# Cable.net
KiCad netlist of a schematic drawn in Altium Designer
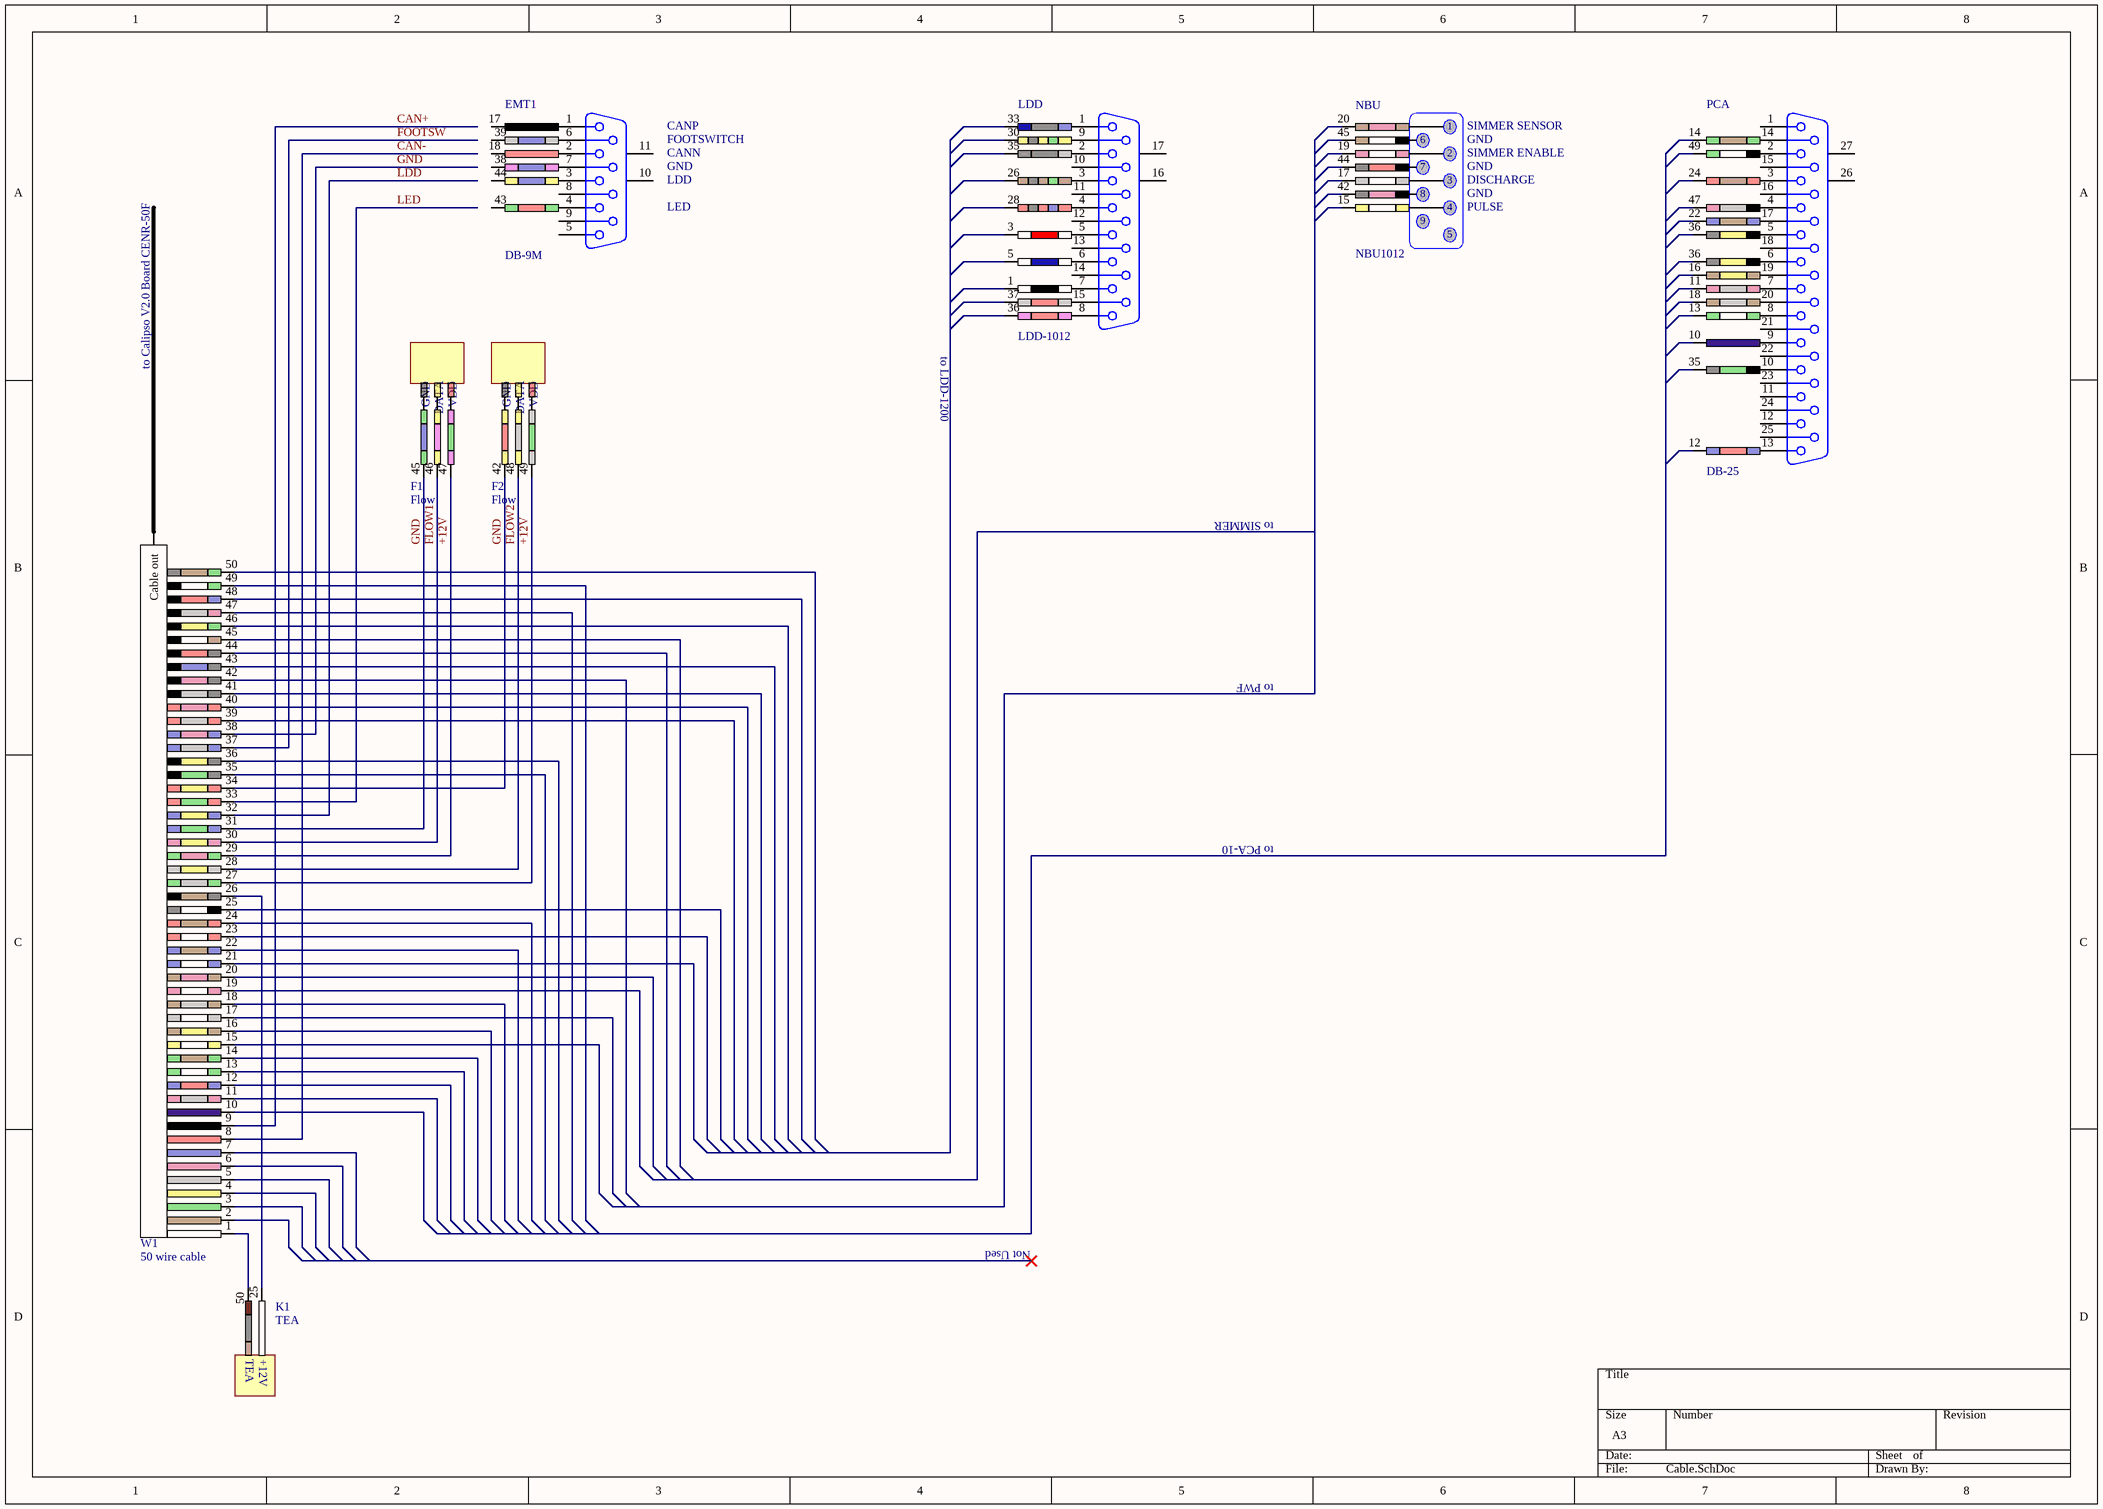
[diagram p0: Cable.SchDoc]

(export (version "E")
  (design (tool "Eeschema 10.0.6"))
  (components
    (comp (ref "EMT1") (value "DB-9M") (libsource (lib "CENR50-LaserCable") (part "Emmiter")))
    (comp (ref "F1")
      (value "Flow")
      (description "Flow sensor")
      (libsource (lib "CENR50-LaserCable") (part "Flow Sensor"))
    )
    (comp (ref "F2")
      (value "Flow")
      (description "Flow sensor 2")
      (libsource (lib "CENR50-LaserCable") (part "Flow Sensor 2"))
    )
    (comp (ref "K1")
      (value "TEA")
      (description "Termo electrical assembly")
      (libsource (lib "CENR50-LaserCable") (part "TEA"))
    )
    (comp (ref "LDD") (value "LDD-1012") (libsource (lib "CENR50-LaserCable") (part "LDD-1012")))
    (comp (ref "NBU") (value "NBU1012") (libsource (lib "CENR50-LaserCable") (part "NBU")))
    (comp (ref "PCA") (value "DB-25") (libsource (lib "CENR50-LaserCable") (part "PCA-10_1")))
    (comp (ref "W1") (value "50 wire cable") (libsource (lib "CENR50-LaserCable") (part "Cable-50wire")))
  )
  (nets
    (net (code "1") (name "/+12V") (class "Default")
      (node (ref "W1") (pin "27") (pinfunction "27_27") (pintype "passive"))
      (node (ref "W1") (pin "29") (pinfunction "29_29") (pintype "passive"))
    )
    (net (code "2") (name "/CAN+") (class "Default")
      (node (ref "W1") (pin "9") (pinfunction "9_9") (pintype "passive"))
    )
    (net (code "3") (name "/CAN-") (class "Default")
      (node (ref "W1") (pin "8") (pinfunction "8_8") (pintype "passive"))
    )
    (net (code "4") (name "/FLOW1") (class "Default")
      (node (ref "W1") (pin "30") (pinfunction "30_30") (pintype "passive"))
    )
    (net (code "5") (name "/FLOW2") (class "Default")
      (node (ref "W1") (pin "28") (pinfunction "28_28") (pintype "passive"))
    )
    (net (code "6") (name "/FOOTSW") (class "Default")
      (node (ref "W1") (pin "37") (pinfunction "37_37") (pintype "passive"))
    )
    (net (code "7") (name "/GND") (class "Default")
      (node (ref "W1") (pin "31") (pinfunction "31_31") (pintype "passive"))
      (node (ref "W1") (pin "34") (pinfunction "34_34") (pintype "passive"))
      (node (ref "W1") (pin "38") (pinfunction "38_38") (pintype "passive"))
    )
    (net (code "8") (name "/LDD") (class "Default")
      (node (ref "W1") (pin "32") (pinfunction "32_32") (pintype "passive"))
    )
    (net (code "9") (name "/LED") (class "Default")
      (node (ref "W1") (pin "33") (pinfunction "33_33") (pintype "passive"))
    )
    (net (code "10") (name "Net-(K1-Pad25)") (class "Default")
      (node (ref "K1") (pin "25") (pinfunction "25_25") (pintype "passive"))
      (node (ref "W1") (pin "26") (pinfunction "26_26") (pintype "passive"))
    )
    (net (code "11") (name "unconnected-(EMT1-MH1-Pad10)") (class "Default")
      (node (ref "EMT1") (pin "10") (pinfunction "MH1_10") (pintype "passive"))
    )
    (net (code "12") (name "unconnected-(EMT1-MH2-Pad11)") (class "Default")
      (node (ref "EMT1") (pin "11") (pinfunction "MH2_11") (pintype "passive"))
    )
    (net (code "13") (name "unconnected-(EMT1-Pad1)") (class "Default")
      (node (ref "EMT1") (pin "1") (pinfunction "1_1") (pintype "passive"))
    )
    (net (code "14") (name "unconnected-(EMT1-Pad2)") (class "Default")
      (node (ref "EMT1") (pin "2") (pinfunction "2_2") (pintype "passive"))
    )
    (net (code "15") (name "unconnected-(EMT1-Pad3)") (class "Default")
      (node (ref "EMT1") (pin "3") (pinfunction "3_3") (pintype "passive"))
    )
    (net (code "16") (name "unconnected-(EMT1-Pad4)") (class "Default")
      (node (ref "EMT1") (pin "4") (pinfunction "4_4") (pintype "passive"))
    )
    (net (code "17") (name "unconnected-(EMT1-Pad5)") (class "Default")
      (node (ref "EMT1") (pin "5") (pinfunction "5_5") (pintype "passive"))
    )
    (net (code "18") (name "unconnected-(EMT1-Pad6)") (class "Default")
      (node (ref "EMT1") (pin "6") (pinfunction "6_6") (pintype "passive"))
    )
    (net (code "19") (name "unconnected-(EMT1-Pad7)") (class "Default")
      (node (ref "EMT1") (pin "7") (pinfunction "7_7") (pintype "passive"))
    )
    (net (code "20") (name "unconnected-(EMT1-Pad8)") (class "Default")
      (node (ref "EMT1") (pin "8") (pinfunction "8_8") (pintype "passive"))
    )
    (net (code "21") (name "unconnected-(EMT1-Pad9)") (class "Default")
      (node (ref "EMT1") (pin "9") (pinfunction "9_9") (pintype "passive"))
    )
    (net (code "22") (name "unconnected-(EMT1-Pad17)") (class "Default")
      (node (ref "EMT1") (pin "17") (pinfunction "17_17") (pintype "passive"))
    )
    (net (code "23") (name "unconnected-(EMT1-Pad18)") (class "Default")
      (node (ref "EMT1") (pin "18") (pinfunction "18_18") (pintype "passive"))
    )
    (net (code "24") (name "unconnected-(EMT1-Pad38)") (class "Default")
      (node (ref "EMT1") (pin "38") (pinfunction "38_38") (pintype "passive"))
    )
    (net (code "25") (name "unconnected-(EMT1-Pad39)") (class "Default")
      (node (ref "EMT1") (pin "39") (pinfunction "39_39") (pintype "passive"))
    )
    (net (code "26") (name "unconnected-(EMT1-Pad43)") (class "Default")
      (node (ref "EMT1") (pin "43") (pinfunction "43_43") (pintype "passive"))
    )
    (net (code "27") (name "unconnected-(EMT1-Pad44)") (class "Default")
      (node (ref "EMT1") (pin "44") (pinfunction "44_44") (pintype "passive"))
    )
    (net (code "28") (name "unconnected-(F1-Pad45)") (class "Default")
      (node (ref "F1") (pin "45") (pinfunction "45_45") (pintype "passive"))
    )
    (net (code "29") (name "unconnected-(F1-Pad46)") (class "Default")
      (node (ref "F1") (pin "46") (pinfunction "46_46") (pintype "passive"))
    )
    (net (code "30") (name "unconnected-(F1-Pad47)") (class "Default")
      (node (ref "F1") (pin "47") (pinfunction "47_47") (pintype "passive"))
    )
    (net (code "31") (name "unconnected-(F2-Pad42)") (class "Default")
      (node (ref "F2") (pin "42") (pinfunction "42_42") (pintype "passive"))
    )
    (net (code "32") (name "unconnected-(F2-Pad48)") (class "Default")
      (node (ref "F2") (pin "48") (pinfunction "48_48") (pintype "passive"))
    )
    (net (code "33") (name "unconnected-(F2-Pad49)") (class "Default")
      (node (ref "F2") (pin "49") (pinfunction "49_49") (pintype "passive"))
    )
    (net (code "34") (name "unconnected-(K1-Pad50)") (class "Default")
      (node (ref "K1") (pin "50") (pinfunction "50_50") (pintype "passive"))
    )
    (net (code "35") (name "unconnected-(LDD-MH1-Pad16)") (class "Default")
      (node (ref "LDD") (pin "16") (pinfunction "MH1_16") (pintype "passive"))
    )
    (net (code "36") (name "unconnected-(LDD-MH2-Pad17)") (class "Default")
      (node (ref "LDD") (pin "17") (pinfunction "MH2_17") (pintype "passive"))
    )
    (net (code "37") (name "unconnected-(LDD-Pad1)") (class "Default")
      (node (ref "LDD") (pin "1") (pinfunction "1_1") (pintype "passive"))
    )
    (net (code "38") (name "unconnected-(LDD-Pad1)_1") (class "Default")
      (node (ref "LDD") (pin "1") (pinfunction "1_1") (pintype "passive"))
    )
    (net (code "39") (name "unconnected-(LDD-Pad2)") (class "Default")
      (node (ref "LDD") (pin "2") (pinfunction "2_2") (pintype "passive"))
    )
    (net (code "40") (name "unconnected-(LDD-Pad3)") (class "Default")
      (node (ref "LDD") (pin "3") (pinfunction "3_3") (pintype "passive"))
    )
    (net (code "41") (name "unconnected-(LDD-Pad3)_1") (class "Default")
      (node (ref "LDD") (pin "3") (pinfunction "3_3") (pintype "passive"))
    )
    (net (code "42") (name "unconnected-(LDD-Pad4)") (class "Default")
      (node (ref "LDD") (pin "4") (pinfunction "4_4") (pintype "passive"))
    )
    (net (code "43") (name "unconnected-(LDD-Pad5)") (class "Default")
      (node (ref "LDD") (pin "5") (pinfunction "5_5") (pintype "passive"))
    )
    (net (code "44") (name "unconnected-(LDD-Pad5)_1") (class "Default")
      (node (ref "LDD") (pin "5") (pinfunction "5_5") (pintype "passive"))
    )
    (net (code "45") (name "unconnected-(LDD-Pad6)") (class "Default")
      (node (ref "LDD") (pin "6") (pinfunction "6_6") (pintype "passive"))
    )
    (net (code "46") (name "unconnected-(LDD-Pad7)") (class "Default")
      (node (ref "LDD") (pin "7") (pinfunction "7_7") (pintype "passive"))
    )
    (net (code "47") (name "unconnected-(LDD-Pad8)") (class "Default")
      (node (ref "LDD") (pin "8") (pinfunction "8_8") (pintype "passive"))
    )
    (net (code "48") (name "unconnected-(LDD-Pad9)") (class "Default")
      (node (ref "LDD") (pin "9") (pinfunction "9_9") (pintype "passive"))
    )
    (net (code "49") (name "unconnected-(LDD-Pad10)") (class "Default")
      (node (ref "LDD") (pin "10") (pinfunction "10_10") (pintype "passive"))
    )
    (net (code "50") (name "unconnected-(LDD-Pad11)") (class "Default")
      (node (ref "LDD") (pin "11") (pinfunction "11_11") (pintype "passive"))
    )
    (net (code "51") (name "unconnected-(LDD-Pad12)") (class "Default")
      (node (ref "LDD") (pin "12") (pinfunction "12_12") (pintype "passive"))
    )
    (net (code "52") (name "unconnected-(LDD-Pad13)") (class "Default")
      (node (ref "LDD") (pin "13") (pinfunction "13_13") (pintype "passive"))
    )
    (net (code "53") (name "unconnected-(LDD-Pad14)") (class "Default")
      (node (ref "LDD") (pin "14") (pinfunction "14_14") (pintype "passive"))
    )
    (net (code "54") (name "unconnected-(LDD-Pad15)") (class "Default")
      (node (ref "LDD") (pin "15") (pinfunction "15_15") (pintype "passive"))
    )
    (net (code "55") (name "unconnected-(LDD-Pad26)") (class "Default")
      (node (ref "LDD") (pin "26") (pinfunction "26_26") (pintype "passive"))
    )
    (net (code "56") (name "unconnected-(LDD-Pad28)") (class "Default")
      (node (ref "LDD") (pin "28") (pinfunction "28_28") (pintype "passive"))
    )
    (net (code "57") (name "unconnected-(LDD-Pad30)") (class "Default")
      (node (ref "LDD") (pin "30") (pinfunction "30_30") (pintype "passive"))
    )
    (net (code "58") (name "unconnected-(LDD-Pad33)") (class "Default")
      (node (ref "LDD") (pin "33") (pinfunction "33_33") (pintype "passive"))
    )
    (net (code "59") (name "unconnected-(LDD-Pad35)") (class "Default")
      (node (ref "LDD") (pin "35") (pinfunction "35_35") (pintype "passive"))
    )
    (net (code "60") (name "unconnected-(LDD-Pad36)") (class "Default")
      (node (ref "LDD") (pin "36") (pinfunction "36_36") (pintype "passive"))
    )
    (net (code "61") (name "unconnected-(LDD-Pad37)") (class "Default")
      (node (ref "LDD") (pin "37") (pinfunction "37_37") (pintype "passive"))
    )
    (net (code "62") (name "unconnected-(NBU-Pad15)") (class "Default")
      (node (ref "NBU") (pin "15") (pinfunction "15_15") (pintype "passive"))
    )
    (net (code "63") (name "unconnected-(NBU-Pad17)") (class "Default")
      (node (ref "NBU") (pin "17") (pinfunction "17_17") (pintype "passive"))
    )
    (net (code "64") (name "unconnected-(NBU-Pad19)") (class "Default")
      (node (ref "NBU") (pin "19") (pinfunction "19_19") (pintype "passive"))
    )
    (net (code "65") (name "unconnected-(NBU-Pad20)") (class "Default")
      (node (ref "NBU") (pin "20") (pinfunction "20_20") (pintype "passive"))
    )
    (net (code "66") (name "unconnected-(NBU-Pad42)") (class "Default")
      (node (ref "NBU") (pin "42") (pinfunction "42_42") (pintype "passive"))
    )
    (net (code "67") (name "unconnected-(NBU-Pad44)") (class "Default")
      (node (ref "NBU") (pin "44") (pinfunction "44_44") (pintype "passive"))
    )
    (net (code "68") (name "unconnected-(NBU-Pad45)") (class "Default")
      (node (ref "NBU") (pin "45") (pinfunction "45_45") (pintype "passive"))
    )
    (net (code "69") (name "unconnected-(PCA-MH1-Pad26)") (class "Default")
      (node (ref "PCA") (pin "26") (pinfunction "MH1_26") (pintype "passive"))
    )
    (net (code "70") (name "unconnected-(PCA-MH2-Pad27)") (class "Default")
      (node (ref "PCA") (pin "27") (pinfunction "MH2_27") (pintype "passive"))
    )
    (net (code "71") (name "unconnected-(PCA-Pad1)") (class "Default")
      (node (ref "PCA") (pin "1") (pinfunction "1_1") (pintype "passive"))
    )
    (net (code "72") (name "unconnected-(PCA-Pad2)") (class "Default")
      (node (ref "PCA") (pin "2") (pinfunction "2_2") (pintype "passive"))
    )
    (net (code "73") (name "unconnected-(PCA-Pad3)") (class "Default")
      (node (ref "PCA") (pin "3") (pinfunction "3_3") (pintype "passive"))
    )
    (net (code "74") (name "unconnected-(PCA-Pad4)") (class "Default")
      (node (ref "PCA") (pin "4") (pinfunction "4_4") (pintype "passive"))
    )
    (net (code "75") (name "unconnected-(PCA-Pad5)") (class "Default")
      (node (ref "PCA") (pin "5") (pinfunction "5_5") (pintype "passive"))
    )
    (net (code "76") (name "unconnected-(PCA-Pad6)") (class "Default")
      (node (ref "PCA") (pin "6") (pinfunction "6_6") (pintype "passive"))
    )
    (net (code "77") (name "unconnected-(PCA-Pad7)") (class "Default")
      (node (ref "PCA") (pin "7") (pinfunction "7_7") (pintype "passive"))
    )
    (net (code "78") (name "unconnected-(PCA-Pad8)") (class "Default")
      (node (ref "PCA") (pin "8") (pinfunction "8_8") (pintype "passive"))
    )
    (net (code "79") (name "unconnected-(PCA-Pad9)") (class "Default")
      (node (ref "PCA") (pin "9") (pinfunction "9_9") (pintype "passive"))
    )
    (net (code "80") (name "unconnected-(PCA-Pad10)") (class "Default")
      (node (ref "PCA") (pin "10") (pinfunction "10_10") (pintype "passive"))
    )
    (net (code "81") (name "unconnected-(PCA-Pad10)_1") (class "Default")
      (node (ref "PCA") (pin "10") (pinfunction "10_10") (pintype "passive"))
    )
    (net (code "82") (name "unconnected-(PCA-Pad11)") (class "Default")
      (node (ref "PCA") (pin "11") (pinfunction "11_11") (pintype "passive"))
    )
    (net (code "83") (name "unconnected-(PCA-Pad11)_1") (class "Default")
      (node (ref "PCA") (pin "11") (pinfunction "11_11") (pintype "passive"))
    )
    (net (code "84") (name "unconnected-(PCA-Pad12)") (class "Default")
      (node (ref "PCA") (pin "12") (pinfunction "12_12") (pintype "passive"))
    )
    (net (code "85") (name "unconnected-(PCA-Pad12)_1") (class "Default")
      (node (ref "PCA") (pin "12") (pinfunction "12_12") (pintype "passive"))
    )
    (net (code "86") (name "unconnected-(PCA-Pad13)") (class "Default")
      (node (ref "PCA") (pin "13") (pinfunction "13_13") (pintype "passive"))
    )
    (net (code "87") (name "unconnected-(PCA-Pad13)_1") (class "Default")
      (node (ref "PCA") (pin "13") (pinfunction "13_13") (pintype "passive"))
    )
    (net (code "88") (name "unconnected-(PCA-Pad14)") (class "Default")
      (node (ref "PCA") (pin "14") (pinfunction "14_14") (pintype "passive"))
    )
    (net (code "89") (name "unconnected-(PCA-Pad14)_1") (class "Default")
      (node (ref "PCA") (pin "14") (pinfunction "14_14") (pintype "passive"))
    )
    (net (code "90") (name "unconnected-(PCA-Pad15)") (class "Default")
      (node (ref "PCA") (pin "15") (pinfunction "15_15") (pintype "passive"))
    )
    (net (code "91") (name "unconnected-(PCA-Pad16)") (class "Default")
      (node (ref "PCA") (pin "16") (pinfunction "16_16") (pintype "passive"))
    )
    (net (code "92") (name "unconnected-(PCA-Pad16)_1") (class "Default")
      (node (ref "PCA") (pin "16") (pinfunction "16_16") (pintype "passive"))
    )
    (net (code "93") (name "unconnected-(PCA-Pad17)") (class "Default")
      (node (ref "PCA") (pin "17") (pinfunction "17_17") (pintype "passive"))
    )
    (net (code "94") (name "unconnected-(PCA-Pad18)") (class "Default")
      (node (ref "PCA") (pin "18") (pinfunction "18_18") (pintype "passive"))
    )
    (net (code "95") (name "unconnected-(PCA-Pad18)_1") (class "Default")
      (node (ref "PCA") (pin "18") (pinfunction "18_18") (pintype "passive"))
    )
    (net (code "96") (name "unconnected-(PCA-Pad19)") (class "Default")
      (node (ref "PCA") (pin "19") (pinfunction "19_19") (pintype "passive"))
    )
    (net (code "97") (name "unconnected-(PCA-Pad20)") (class "Default")
      (node (ref "PCA") (pin "20") (pinfunction "20_20") (pintype "passive"))
    )
    (net (code "98") (name "unconnected-(PCA-Pad21)") (class "Default")
      (node (ref "PCA") (pin "21") (pinfunction "21_21") (pintype "passive"))
    )
    (net (code "99") (name "unconnected-(PCA-Pad22)") (class "Default")
      (node (ref "PCA") (pin "22") (pinfunction "22_22") (pintype "passive"))
    )
    (net (code "100") (name "unconnected-(PCA-Pad22)_1") (class "Default")
      (node (ref "PCA") (pin "22") (pinfunction "22_22") (pintype "passive"))
    )
    (net (code "101") (name "unconnected-(PCA-Pad23)") (class "Default")
      (node (ref "PCA") (pin "23") (pinfunction "23_23") (pintype "passive"))
    )
    (net (code "102") (name "unconnected-(PCA-Pad24)") (class "Default")
      (node (ref "PCA") (pin "24") (pinfunction "24_24") (pintype "passive"))
    )
    (net (code "103") (name "unconnected-(PCA-Pad24)_1") (class "Default")
      (node (ref "PCA") (pin "24") (pinfunction "24_24") (pintype "passive"))
    )
    (net (code "104") (name "unconnected-(PCA-Pad25)") (class "Default")
      (node (ref "PCA") (pin "25") (pinfunction "25_25") (pintype "passive"))
    )
    (net (code "105") (name "unconnected-(PCA-Pad35)") (class "Default")
      (node (ref "PCA") (pin "35") (pinfunction "35_35") (pintype "passive"))
    )
    (net (code "106") (name "unconnected-(PCA-Pad36)") (class "Default")
      (node (ref "PCA") (pin "36") (pinfunction "36_36") (pintype "passive"))
    )
    (net (code "107") (name "unconnected-(PCA-Pad36)_1") (class "Default")
      (node (ref "PCA") (pin "36") (pinfunction "36_36") (pintype "passive"))
    )
    (net (code "108") (name "unconnected-(PCA-Pad47)") (class "Default")
      (node (ref "PCA") (pin "47") (pinfunction "47_47") (pintype "passive"))
    )
    (net (code "109") (name "unconnected-(PCA-Pad49)") (class "Default")
      (node (ref "PCA") (pin "49") (pinfunction "49_49") (pintype "passive"))
    )
    (net (code "110") (name "unconnected-(W1-Cable_out-Pad51)") (class "Default")
      (node (ref "W1") (pin "51") (pinfunction "Cable_out_51") (pintype "passive"))
    )
    (net (code "111") (name "unconnected-(W1-Pad1)") (class "Default")
      (node (ref "W1") (pin "1") (pinfunction "1_1") (pintype "passive"))
    )
    (net (code "112") (name "unconnected-(W1-Pad2)") (class "Default")
      (node (ref "W1") (pin "2") (pinfunction "2_2") (pintype "passive"))
    )
    (net (code "113") (name "unconnected-(W1-Pad3)") (class "Default")
      (node (ref "W1") (pin "3") (pinfunction "3_3") (pintype "passive"))
    )
    (net (code "114") (name "unconnected-(W1-Pad4)") (class "Default")
      (node (ref "W1") (pin "4") (pinfunction "4_4") (pintype "passive"))
    )
    (net (code "115") (name "unconnected-(W1-Pad5)") (class "Default")
      (node (ref "W1") (pin "5") (pinfunction "5_5") (pintype "passive"))
    )
    (net (code "116") (name "unconnected-(W1-Pad6)") (class "Default")
      (node (ref "W1") (pin "6") (pinfunction "6_6") (pintype "passive"))
    )
    (net (code "117") (name "unconnected-(W1-Pad7)") (class "Default")
      (node (ref "W1") (pin "7") (pinfunction "7_7") (pintype "passive"))
    )
    (net (code "118") (name "unconnected-(W1-Pad10)") (class "Default")
      (node (ref "W1") (pin "10") (pinfunction "10_10") (pintype "passive"))
    )
    (net (code "119") (name "unconnected-(W1-Pad11)") (class "Default")
      (node (ref "W1") (pin "11") (pinfunction "11_11") (pintype "passive"))
    )
    (net (code "120") (name "unconnected-(W1-Pad12)") (class "Default")
      (node (ref "W1") (pin "12") (pinfunction "12_12") (pintype "passive"))
    )
    (net (code "121") (name "unconnected-(W1-Pad13)") (class "Default")
      (node (ref "W1") (pin "13") (pinfunction "13_13") (pintype "passive"))
    )
    (net (code "122") (name "unconnected-(W1-Pad14)") (class "Default")
      (node (ref "W1") (pin "14") (pinfunction "14_14") (pintype "passive"))
    )
    (net (code "123") (name "unconnected-(W1-Pad15)") (class "Default")
      (node (ref "W1") (pin "15") (pinfunction "15_15") (pintype "passive"))
    )
    (net (code "124") (name "unconnected-(W1-Pad16)") (class "Default")
      (node (ref "W1") (pin "16") (pinfunction "16_16") (pintype "passive"))
    )
    (net (code "125") (name "unconnected-(W1-Pad17)") (class "Default")
      (node (ref "W1") (pin "17") (pinfunction "17_17") (pintype "passive"))
    )
    (net (code "126") (name "unconnected-(W1-Pad18)") (class "Default")
      (node (ref "W1") (pin "18") (pinfunction "18_18") (pintype "passive"))
    )
    (net (code "127") (name "unconnected-(W1-Pad19)") (class "Default")
      (node (ref "W1") (pin "19") (pinfunction "19_19") (pintype "passive"))
    )
    (net (code "128") (name "unconnected-(W1-Pad20)") (class "Default")
      (node (ref "W1") (pin "20") (pinfunction "20_20") (pintype "passive"))
    )
    (net (code "129") (name "unconnected-(W1-Pad21)") (class "Default")
      (node (ref "W1") (pin "21") (pinfunction "21_21") (pintype "passive"))
    )
    (net (code "130") (name "unconnected-(W1-Pad22)") (class "Default")
      (node (ref "W1") (pin "22") (pinfunction "22_22") (pintype "passive"))
    )
    (net (code "131") (name "unconnected-(W1-Pad23)") (class "Default")
      (node (ref "W1") (pin "23") (pinfunction "23_23") (pintype "passive"))
    )
    (net (code "132") (name "unconnected-(W1-Pad24)") (class "Default")
      (node (ref "W1") (pin "24") (pinfunction "24_24") (pintype "passive"))
    )
    (net (code "133") (name "unconnected-(W1-Pad25)") (class "Default")
      (node (ref "W1") (pin "25") (pinfunction "25_25") (pintype "passive"))
    )
    (net (code "134") (name "unconnected-(W1-Pad35)") (class "Default")
      (node (ref "W1") (pin "35") (pinfunction "35_35") (pintype "passive"))
    )
    (net (code "135") (name "unconnected-(W1-Pad36)") (class "Default")
      (node (ref "W1") (pin "36") (pinfunction "36_36") (pintype "passive"))
    )
    (net (code "136") (name "unconnected-(W1-Pad39)") (class "Default")
      (node (ref "W1") (pin "39") (pinfunction "39_39") (pintype "passive"))
    )
    (net (code "137") (name "unconnected-(W1-Pad40)") (class "Default")
      (node (ref "W1") (pin "40") (pinfunction "40_40") (pintype "passive"))
    )
    (net (code "138") (name "unconnected-(W1-Pad41)") (class "Default")
      (node (ref "W1") (pin "41") (pinfunction "41_41") (pintype "passive"))
    )
    (net (code "139") (name "unconnected-(W1-Pad42)") (class "Default")
      (node (ref "W1") (pin "42") (pinfunction "42_42") (pintype "passive"))
    )
    (net (code "140") (name "unconnected-(W1-Pad43)") (class "Default")
      (node (ref "W1") (pin "43") (pinfunction "43_43") (pintype "passive"))
    )
    (net (code "141") (name "unconnected-(W1-Pad44)") (class "Default")
      (node (ref "W1") (pin "44") (pinfunction "44_44") (pintype "passive"))
    )
    (net (code "142") (name "unconnected-(W1-Pad45)") (class "Default")
      (node (ref "W1") (pin "45") (pinfunction "45_45") (pintype "passive"))
    )
    (net (code "143") (name "unconnected-(W1-Pad46)") (class "Default")
      (node (ref "W1") (pin "46") (pinfunction "46_46") (pintype "passive"))
    )
    (net (code "144") (name "unconnected-(W1-Pad47)") (class "Default")
      (node (ref "W1") (pin "47") (pinfunction "47_47") (pintype "passive"))
    )
    (net (code "145") (name "unconnected-(W1-Pad48)") (class "Default")
      (node (ref "W1") (pin "48") (pinfunction "48_48") (pintype "passive"))
    )
    (net (code "146") (name "unconnected-(W1-Pad49)") (class "Default")
      (node (ref "W1") (pin "49") (pinfunction "49_49") (pintype "passive"))
    )
    (net (code "147") (name "unconnected-(W1-Pad50)") (class "Default")
      (node (ref "W1") (pin "50") (pinfunction "50_50") (pintype "passive"))
    )
  )
)
